# ArduiPi.net
KiCad netlist of a schematic drawn in EAGLE
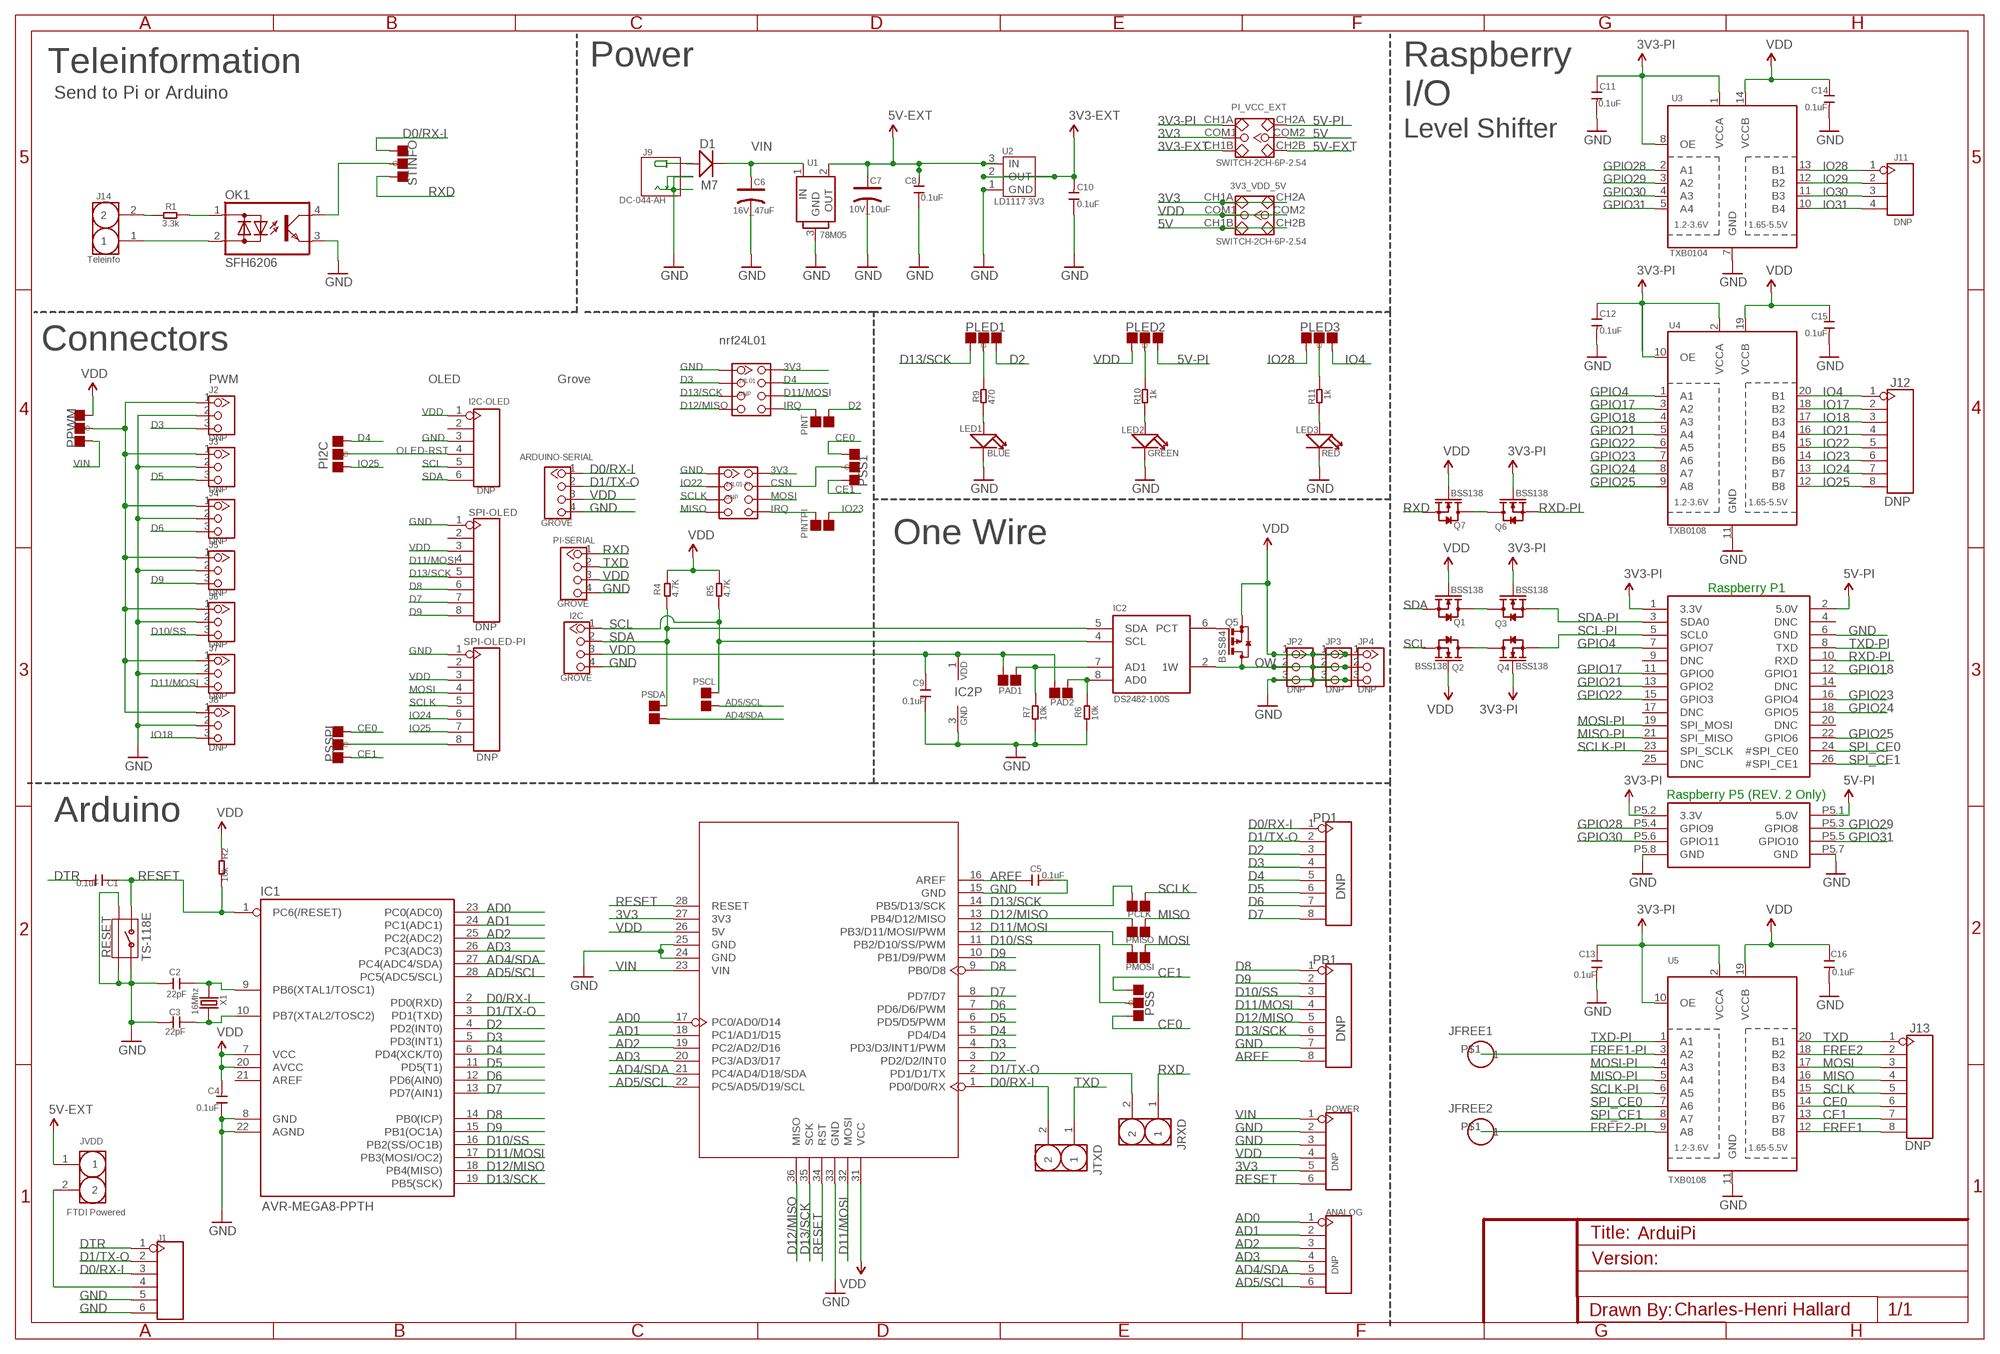
[diagram p0: schematic, sheet 1]

(export (version "E")
  (design (tool "Eeschema 10.0.6"))
  (components
    (comp (ref "3V3_VDD_5V")
      (value "SWITCH-2CH-6P-2.54")
      (footprint "eagle-import:6P-2CH-2.54-7.6X3.0")
      (libsource (lib "eagle-import") (part "SWITCH-2CH-6P"))
    )
    (comp (ref "24L01")
      (value "DNP")
      (footprint "eagle-import:2X4P-2.54")
      (libsource (lib "eagle-import") (part "HEADER-2X4P-2.54"))
    )
    (comp (ref "24L01-PI")
      (value "DNP")
      (footprint "eagle-import:2X4P-2.54")
      (libsource (lib "eagle-import") (part "HEADER-2X4P-2.54"))
    )
    (comp (ref "ANALOG")
      (value "DNP")
      (footprint "eagle-import:6P-2.54-65_35MIL")
      (libsource (lib "eagle-import") (part "HEADER-6P-65/35MIL"))
    )
    (comp (ref "ARDUINO-SERIAL")
      (value "GROVE")
      (footprint "eagle-import:4P-LEADED-2.0")
      (libsource (lib "eagle-import") (part "TWIG-2.0-LEADED"))
    )
    (comp (ref "C1")
      (value "0.1uF")
      (footprint "eagle-import:C0603")
      (libsource (lib "eagle-import") (part "C-0603"))
    )
    (comp (ref "C2")
      (value "22pF")
      (footprint "eagle-import:C0603")
      (libsource (lib "eagle-import") (part "C-0603"))
    )
    (comp (ref "C3")
      (value "22pF")
      (footprint "eagle-import:C0603")
      (libsource (lib "eagle-import") (part "C-0603"))
    )
    (comp (ref "C4")
      (value "0.1uF")
      (footprint "eagle-import:C0603")
      (libsource (lib "eagle-import") (part "C-0603"))
    )
    (comp (ref "C5")
      (value "0.1uF")
      (footprint "eagle-import:C0603")
      (libsource (lib "eagle-import") (part "C-0603"))
    )
    (comp (ref "C6")
      (value "16V_47uF")
      (footprint "eagle-import:AVX-C")
      (libsource (lib "eagle-import") (part "CAP-AVX-C"))
    )
    (comp (ref "C7")
      (value "10V_10uF")
      (footprint "eagle-import:AVX-A")
      (libsource (lib "eagle-import") (part "CAP-AVX-A"))
    )
    (comp (ref "C8")
      (value "0.1uF")
      (footprint "eagle-import:C0603")
      (libsource (lib "eagle-import") (part "C-0603"))
    )
    (comp (ref "C9")
      (value "0.1uF")
      (footprint "eagle-import:C0603")
      (libsource (lib "eagle-import") (part "C-0603"))
    )
    (comp (ref "C10")
      (value "0.1uF")
      (footprint "eagle-import:C0603")
      (libsource (lib "eagle-import") (part "C-0603"))
    )
    (comp (ref "C11")
      (value "0.1uF")
      (footprint "eagle-import:C0603")
      (libsource (lib "eagle-import") (part "C-0603"))
    )
    (comp (ref "C12")
      (value "0.1uF")
      (footprint "eagle-import:C0603")
      (libsource (lib "eagle-import") (part "C-0603"))
    )
    (comp (ref "C13")
      (value "0.1uF")
      (footprint "eagle-import:C0603")
      (libsource (lib "eagle-import") (part "C-0603"))
    )
    (comp (ref "C14")
      (value "0.1uF")
      (footprint "eagle-import:C0603")
      (libsource (lib "eagle-import") (part "C-0603"))
    )
    (comp (ref "C15")
      (value "0.1uF")
      (footprint "eagle-import:C0603")
      (libsource (lib "eagle-import") (part "C-0603"))
    )
    (comp (ref "C16")
      (value "0.1uF")
      (footprint "eagle-import:C0603")
      (libsource (lib "eagle-import") (part "C-0603"))
    )
    (comp (ref "D1")
      (value "M7")
      (footprint "eagle-import:D2010")
      (libsource (lib "eagle-import") (part "D'SMA'"))
    )
    (comp (ref "I2C")
      (value "GROVE")
      (footprint "eagle-import:4P-LEADED-2.0")
      (libsource (lib "eagle-import") (part "TWIG-2.0-LEADED"))
    )
    (comp (ref "I2C-OLED")
      (value "DNP")
      (footprint "eagle-import:6P-2.54-65_35MIL")
      (libsource (lib "eagle-import") (part "HEADER-6P-65/35MIL"))
    )
    (comp (ref "IC1")
      (value "AVR-MEGA8-PPTH")
      (footprint "eagle-import:DIL28-3")
      (libsource (lib "eagle-import") (part "AVR-MEGA8-PPTH"))
    )
    (comp (ref "IC2")
      (value "DS2482-100S")
      (footprint "eagle-import:SO08")
      (libsource (lib "eagle-import") (part "DS2482-100S"))
    )
    (comp (ref "J1")
      (value "HEADER-6P-65/35MIL")
      (footprint "eagle-import:6P-2.54-65_35MIL")
      (libsource (lib "eagle-import") (part "HEADER-6P-65/35MIL"))
    )
    (comp (ref "J2")
      (value "DNP")
      (footprint "eagle-import:3P-2.54")
      (libsource (lib "eagle-import") (part "HEADER-3P-2.54"))
    )
    (comp (ref "J3")
      (value "DNP")
      (footprint "eagle-import:3P-2.54")
      (libsource (lib "eagle-import") (part "HEADER-3P-2.54"))
    )
    (comp (ref "J4")
      (value "DNP")
      (footprint "eagle-import:3P-2.54")
      (libsource (lib "eagle-import") (part "HEADER-3P-2.54"))
    )
    (comp (ref "J5")
      (value "DNP")
      (footprint "eagle-import:3P-2.54")
      (libsource (lib "eagle-import") (part "HEADER-3P-2.54"))
    )
    (comp (ref "J6")
      (value "DNP")
      (footprint "eagle-import:3P-2.54")
      (libsource (lib "eagle-import") (part "HEADER-3P-2.54"))
    )
    (comp (ref "J7")
      (value "DNP")
      (footprint "eagle-import:3P-2.54")
      (libsource (lib "eagle-import") (part "HEADER-3P-2.54"))
    )
    (comp (ref "J8")
      (value "DNP")
      (footprint "eagle-import:3P-2.54")
      (libsource (lib "eagle-import") (part "HEADER-3P-2.54"))
    )
    (comp (ref "J9")
      (value "DC-044-AH")
      (footprint "eagle-import:DC-044")
      (libsource (lib "eagle-import") (part "JACK-DC-044"))
    )
    (comp (ref "J11")
      (value "DNP")
      (footprint "eagle-import:4P-65_35MIL")
      (libsource (lib "eagle-import") (part "HEADER-4P-65/35MIL"))
    )
    (comp (ref "J12")
      (value "DNP")
      (footprint "eagle-import:8P-2.54-65_35MIL")
      (libsource (lib "eagle-import") (part "HEADER-8P-65/35MIL"))
    )
    (comp (ref "J13")
      (value "DNP")
      (footprint "eagle-import:8P-2.54-65_35MIL")
      (libsource (lib "eagle-import") (part "HEADER-8P-65/35MIL"))
    )
    (comp (ref "J14")
      (value "Teleinfo")
      (footprint "eagle-import:2P-2.54")
      (libsource (lib "eagle-import") (part "HEADER-2P-2.54"))
    )
    (comp (ref "JFREE1")
      (value "HEADER-1P-32")
      (footprint "eagle-import:1P-60_32MIL")
      (libsource (lib "eagle-import") (part "HEADER-1P-32"))
    )
    (comp (ref "JFREE2")
      (value "HEADER-1P-32")
      (footprint "eagle-import:1P-60_32MIL")
      (libsource (lib "eagle-import") (part "HEADER-1P-32"))
    )
    (comp (ref "JP2")
      (value "DNP")
      (footprint "eagle-import:3P-2.54")
      (libsource (lib "eagle-import") (part "HEADER-3P-2.54"))
    )
    (comp (ref "JP3")
      (value "DNP")
      (footprint "eagle-import:3P-2.54")
      (libsource (lib "eagle-import") (part "HEADER-3P-2.54"))
    )
    (comp (ref "JP4")
      (value "DNP")
      (footprint "eagle-import:3P-2.54")
      (libsource (lib "eagle-import") (part "HEADER-3P-2.54"))
    )
    (comp (ref "JRXD")
      (value "J2")
      (footprint "eagle-import:2P-2.54")
      (libsource (lib "eagle-import") (part "HEADER-2P-2.54"))
    )
    (comp (ref "JTXD")
      (value "J1")
      (footprint "eagle-import:2P-2.54")
      (libsource (lib "eagle-import") (part "HEADER-2P-2.54"))
    )
    (comp (ref "JVDD")
      (value "FTDI Powered")
      (footprint "eagle-import:2P-2.54")
      (libsource (lib "eagle-import") (part "HEADER-2P-2.54"))
    )
    (comp (ref "LED1")
      (value "BLUE")
      (footprint "eagle-import:LED-0603")
      (libsource (lib "eagle-import") (part "LED'0603'"))
    )
    (comp (ref "LED2")
      (value "GREEN")
      (footprint "eagle-import:LED-0603")
      (libsource (lib "eagle-import") (part "LED'0603'"))
    )
    (comp (ref "LED3")
      (value "RED")
      (footprint "eagle-import:LED-0603")
      (libsource (lib "eagle-import") (part "LED'0603'"))
    )
    (comp (ref "OK1")
      (value "SFH6206")
      (footprint "eagle-import:DIL4-SMD")
      (fields (field (name "MF") "VISHAY/TELEFUNKEN") (field (name "MPN") "SFH6206-3"))
      (libsource (lib "eagle-import") (part "SFH6206"))
    )
    (comp (ref "PAD1")
      (value "PAD1")
      (footprint "eagle-import:2P-SMD-1.78X1.27")
      (fields (field (name "PARTNO") "DNP") (field (name "PARTNO_1") "DNP"))
      (libsource (lib "eagle-import") (part "PAD-JUMPER-2P"))
    )
    (comp (ref "PAD2")
      (value "PAD2")
      (footprint "eagle-import:2P-SMD-1.78X1.27")
      (fields (field (name "PARTNO") "DNP") (field (name "PARTNO_1") "DNP"))
      (libsource (lib "eagle-import") (part "PAD-JUMPER-2P"))
    )
    (comp (ref "PB1")
      (value "DNP")
      (footprint "eagle-import:8P-2.54-65_35MIL")
      (libsource (lib "eagle-import") (part "HEADER-8P-65/35MIL"))
    )
    (comp (ref "PCLK")
      (value "PCLK")
      (footprint "eagle-import:2P-SMD-1.78X1.27")
      (fields (field (name "PARTNO") "DNP"))
      (libsource (lib "eagle-import") (part "PAD-JUMPER-2P"))
    )
    (comp (ref "PD1")
      (value "DNP")
      (footprint "eagle-import:8P-2.54-65_35MIL")
      (libsource (lib "eagle-import") (part "HEADER-8P-65/35MIL"))
    )
    (comp (ref "PI-P1")
      (value "PI-P1")
      (footprint "eagle-import:RASPBERRYPI_SHIELD")
      (libsource (lib "eagle-import") (part "RASPBERRYPI_BV2"))
    )
    (comp (ref "PI-SERIAL")
      (value "GROVE")
      (footprint "eagle-import:4P-LEADED-2.0")
      (libsource (lib "eagle-import") (part "TWIG-2.0-LEADED"))
    )
    (comp (ref "PI2C")
      (value "PAD-JUMPER-3P-40*40")
      (footprint "eagle-import:3P-SMD-4.1X1.5")
      (fields (field (name "PARTNO") "DNP") (field (name "PARTNO_1") "DNP"))
      (libsource (lib "eagle-import") (part "PAD-JUMPER-3P-4040"))
    )
    (comp (ref "PINT")
      (value "PINT")
      (footprint "eagle-import:2P-SMD-1.78X1.27")
      (fields (field (name "PARTNO") "DNP"))
      (libsource (lib "eagle-import") (part "PAD-JUMPER-2P"))
    )
    (comp (ref "PINTPI")
      (value "PINTPI")
      (footprint "eagle-import:2P-SMD-1.78X1.27")
      (fields (field (name "PARTNO") "DNP"))
      (libsource (lib "eagle-import") (part "PAD-JUMPER-2P"))
    )
    (comp (ref "PI_VCC_EXT")
      (value "SWITCH-2CH-6P-2.54")
      (footprint "eagle-import:6P-2CH-2.54-7.6X3.0")
      (libsource (lib "eagle-import") (part "SWITCH-2CH-6P"))
    )
    (comp (ref "PLED1")
      (value "PAD-JUMPER-3P-40*40")
      (footprint "eagle-import:3P-SMD-4.1X1.5")
      (fields (field (name "PARTNO") "DNP") (field (name "PARTNO_1") "DNP"))
      (libsource (lib "eagle-import") (part "PAD-JUMPER-3P-4040"))
    )
    (comp (ref "PLED2")
      (value "PAD-JUMPER-3P-40*40")
      (footprint "eagle-import:3P-SMD-4.1X1.5")
      (fields (field (name "PARTNO") "DNP"))
      (libsource (lib "eagle-import") (part "PAD-JUMPER-3P-4040"))
    )
    (comp (ref "PLED3")
      (value "PAD-JUMPER-3P-40*40")
      (footprint "eagle-import:3P-SMD-4.1X1.5")
      (fields (field (name "PARTNO") "DNP") (field (name "PARTNO_1") "DNP"))
      (libsource (lib "eagle-import") (part "PAD-JUMPER-3P-4040"))
    )
    (comp (ref "PMISO")
      (value "PMISO")
      (footprint "eagle-import:2P-SMD-1.78X1.27")
      (fields (field (name "PARTNO") "DNP"))
      (libsource (lib "eagle-import") (part "PAD-JUMPER-2P"))
    )
    (comp (ref "PMOSI")
      (value "PMOSI")
      (footprint "eagle-import:2P-SMD-1.78X1.27")
      (fields (field (name "PARTNO") "DNP"))
      (libsource (lib "eagle-import") (part "PAD-JUMPER-2P"))
    )
    (comp (ref "POWER")
      (value "DNP")
      (footprint "eagle-import:6P-2.54-65_35MIL")
      (libsource (lib "eagle-import") (part "HEADER-6P-65/35MIL"))
    )
    (comp (ref "PPWM")
      (value "PAD-JUMPER-3P-40*40")
      (footprint "eagle-import:3P-SMD-4.1X1.5")
      (fields (field (name "PARTNO") "DNP") (field (name "PARTNO_1") "DNP"))
      (libsource (lib "eagle-import") (part "PAD-JUMPER-3P-4040"))
    )
    (comp (ref "PSCL")
      (value "PSCL")
      (footprint "eagle-import:2P-SMD-1.78X1.27")
      (fields (field (name "PARTNO") "DNP"))
      (libsource (lib "eagle-import") (part "PAD-JUMPER-2P"))
    )
    (comp (ref "PSDA")
      (value "PSDA")
      (footprint "eagle-import:2P-SMD-1.78X1.27")
      (fields (field (name "PARTNO") "DNP"))
      (libsource (lib "eagle-import") (part "PAD-JUMPER-2P"))
    )
    (comp (ref "PSS")
      (value "PAD-JUMPER-3P-40*40")
      (footprint "eagle-import:3P-SMD-4.1X1.5")
      (fields (field (name "PARTNO") "DNP"))
      (libsource (lib "eagle-import") (part "PAD-JUMPER-3P-4040"))
    )
    (comp (ref "PSS1")
      (value "PAD-JUMPER-3P-40*40")
      (footprint "eagle-import:3P-SMD-4.1X1.5")
      (fields (field (name "PARTNO") "DNP") (field (name "PARTNO_1") "DNP"))
      (libsource (lib "eagle-import") (part "PAD-JUMPER-3P-4040"))
    )
    (comp (ref "PSSPI")
      (value "PAD-JUMPER-3P-40*40")
      (footprint "eagle-import:3P-SMD-4.1X1.5")
      (fields (field (name "PARTNO") "DNP") (field (name "PARTNO_1") "DNP"))
      (libsource (lib "eagle-import") (part "PAD-JUMPER-3P-4040"))
    )
    (comp (ref "Q1")
      (value "BSS138")
      (footprint "eagle-import:SOT23")
      (libsource (lib "eagle-import") (part "MOSFET-N-SOT23"))
    )
    (comp (ref "Q2")
      (value "BSS138")
      (footprint "eagle-import:SOT23")
      (libsource (lib "eagle-import") (part "MOSFET-N-SOT23"))
    )
    (comp (ref "Q3")
      (value "BSS138")
      (footprint "eagle-import:SOT23")
      (libsource (lib "eagle-import") (part "MOSFET-N-SOT23"))
    )
    (comp (ref "Q4")
      (value "BSS138")
      (footprint "eagle-import:SOT23")
      (libsource (lib "eagle-import") (part "MOSFET-N-SOT23"))
    )
    (comp (ref "Q5")
      (value "BSS84")
      (footprint "eagle-import:SOT23")
      (libsource (lib "eagle-import") (part "BSS84"))
    )
    (comp (ref "Q6")
      (value "BSS138")
      (footprint "eagle-import:SOT23")
      (libsource (lib "eagle-import") (part "MOSFET-N-SOT23"))
    )
    (comp (ref "Q7")
      (value "BSS138")
      (footprint "eagle-import:SOT23")
      (libsource (lib "eagle-import") (part "MOSFET-N-SOT23"))
    )
    (comp (ref "R1")
      (value "3.3k")
      (footprint "eagle-import:R0603")
      (libsource (lib "eagle-import") (part "R-0603"))
    )
    (comp (ref "R2")
      (value "10k")
      (footprint "eagle-import:R0603")
      (libsource (lib "eagle-import") (part "R-0603"))
    )
    (comp (ref "R4")
      (value "4.7K")
      (footprint "eagle-import:R0603")
      (libsource (lib "eagle-import") (part "R-0603"))
    )
    (comp (ref "R5")
      (value "4.7K")
      (footprint "eagle-import:R0603")
      (libsource (lib "eagle-import") (part "R-0603"))
    )
    (comp (ref "R6")
      (value "10k")
      (footprint "eagle-import:R0603")
      (libsource (lib "eagle-import") (part "R-0603"))
    )
    (comp (ref "R7")
      (value "10k")
      (footprint "eagle-import:R0603")
      (libsource (lib "eagle-import") (part "R-0603"))
    )
    (comp (ref "R9")
      (value "470")
      (footprint "eagle-import:R0603")
      (libsource (lib "eagle-import") (part "R-0603"))
    )
    (comp (ref "R10")
      (value "1k")
      (footprint "eagle-import:R0603")
      (libsource (lib "eagle-import") (part "R-0603"))
    )
    (comp (ref "R11")
      (value "1k")
      (footprint "eagle-import:R0603")
      (libsource (lib "eagle-import") (part "R-0603"))
    )
    (comp (ref "RESET")
      (value "TS-118E")
      (footprint "eagle-import:4P-SMD-7X3.5X3.5H")
      (libsource (lib "eagle-import") (part "BUTTON-4P-REINFORCE'TS-118E'"))
    )
    (comp (ref "SPI-OLED")
      (value "DNP")
      (footprint "eagle-import:8P-2.54-65_35MIL")
      (libsource (lib "eagle-import") (part "HEADER-8P-65/35MIL"))
    )
    (comp (ref "SPI-OLED-PI")
      (value "DNP")
      (footprint "eagle-import:8P-2.54-65_35MIL")
      (libsource (lib "eagle-import") (part "HEADER-8P-65/35MIL"))
    )
    (comp (ref "STINFO")
      (value "PAD-JUMPER-3P-40*40")
      (footprint "eagle-import:3P-SMD-4.1X1.5")
      (fields (field (name "PARTNO") "DNP"))
      (libsource (lib "eagle-import") (part "PAD-JUMPER-3P-4040"))
    )
    (comp (ref "U1")
      (value "78M05")
      (footprint "eagle-import:TO252")
      (libsource (lib "eagle-import") (part "78M05-TO252"))
    )
    (comp (ref "U2")
      (value "LD1117 3V3")
      (footprint "eagle-import:SOT-223")
      (libsource (lib "eagle-import") (part "LD1117SOT223"))
    )
    (comp (ref "U3")
      (value "TXB0104")
      (footprint "eagle-import:TSSOP14")
      (libsource (lib "eagle-import") (part "TXB0104PWR"))
    )
    (comp (ref "U4")
      (value "TXB0108")
      (footprint "eagle-import:TSSOP20")
      (libsource (lib "eagle-import") (part "TXB0108PWR"))
    )
    (comp (ref "U5")
      (value "TXB0108")
      (footprint "eagle-import:TSSOP20")
      (libsource (lib "eagle-import") (part "TXB0108PWR"))
    )
    (comp (ref "U6")
      (value "ARDUINO'W/-SILK")
      (footprint "eagle-import:ARDUINO")
      (libsource (lib "eagle-import") (part "ARDUINO'W/-SILK"))
    )
    (comp (ref "X1")
      (value "16Mhz")
      (footprint "eagle-import:2P-SMD-5X3.2")
      (libsource (lib "eagle-import") (part "CRYSTAL'5032'"))
    )
  )
  (nets
    (net (code "1") (name "/3V3") (class "Default")
      (node (ref "24L01") (pin "8") (pinfunction "8_8") (pintype "bidirectional"))
      (node (ref "24L01-PI") (pin "8") (pinfunction "8_8") (pintype "bidirectional"))
      (node (ref "3V3_VDD_5V") (pin "CH1A") (pinfunction "CH1A_CH1A") (pintype "bidirectional"))
      (node (ref "3V3_VDD_5V") (pin "CH2A") (pinfunction "CH2A_CH2A") (pintype "bidirectional"))
      (node (ref "PI_VCC_EXT") (pin "COM1") (pinfunction "COM1_COM1") (pintype "bidirectional"))
      (node (ref "POWER") (pin "5") (pinfunction "5_5") (pintype "bidirectional"))
      (node (ref "U6") (pin "27") (pinfunction "3V3_27") (pintype "bidirectional"))
    )
    (net (code "2") (name "/5V") (class "Default")
      (node (ref "3V3_VDD_5V") (pin "CH1B") (pinfunction "CH1B_CH1B") (pintype "bidirectional"))
      (node (ref "3V3_VDD_5V") (pin "CH2B") (pinfunction "CH2B_CH2B") (pintype "bidirectional"))
      (node (ref "PI_VCC_EXT") (pin "COM2") (pinfunction "COM2_COM2") (pintype "bidirectional"))
    )
    (net (code "3") (name "/AD0") (class "Default")
      (node (ref "ANALOG") (pin "1") (pinfunction "1_1") (pintype "bidirectional"))
      (node (ref "IC1") (pin "23") (pinfunction "PC0(ADC0)_23") (pintype "bidirectional"))
      (node (ref "U6") (pin "17") (pinfunction "PC0/AD0/D14_17") (pintype "bidirectional"))
    )
    (net (code "4") (name "/AD1") (class "Default")
      (node (ref "ANALOG") (pin "2") (pinfunction "2_2") (pintype "bidirectional"))
      (node (ref "IC1") (pin "24") (pinfunction "PC1(ADC1)_24") (pintype "bidirectional"))
      (node (ref "U6") (pin "18") (pinfunction "PC1/AD1/D15_18") (pintype "bidirectional"))
    )
    (net (code "5") (name "/AD2") (class "Default")
      (node (ref "ANALOG") (pin "3") (pinfunction "3_3") (pintype "bidirectional"))
      (node (ref "IC1") (pin "25") (pinfunction "PC2(ADC2)_25") (pintype "bidirectional"))
      (node (ref "U6") (pin "19") (pinfunction "PC2/AD2/D16_19") (pintype "bidirectional"))
    )
    (net (code "6") (name "/AD3") (class "Default")
      (node (ref "ANALOG") (pin "4") (pinfunction "4_4") (pintype "bidirectional"))
      (node (ref "IC1") (pin "26") (pinfunction "PC3(ADC3)_26") (pintype "bidirectional"))
      (node (ref "U6") (pin "20") (pinfunction "PC3/AD3/D17_20") (pintype "bidirectional"))
    )
    (net (code "7") (name "/AD4{slash}SDA") (class "Default")
      (node (ref "ANALOG") (pin "5") (pinfunction "5_5") (pintype "bidirectional"))
      (node (ref "IC1") (pin "27") (pinfunction "PC4(ADC4/SDA)_27") (pintype "bidirectional"))
      (node (ref "PSDA") (pin "1") (pinfunction "1_1") (pintype "bidirectional"))
      (node (ref "U6") (pin "21") (pinfunction "PC4/AD4/D18/SDA_21") (pintype "bidirectional"))
    )
    (net (code "8") (name "/AD5{slash}SCL") (class "Default")
      (node (ref "ANALOG") (pin "6") (pinfunction "6_6") (pintype "bidirectional"))
      (node (ref "IC1") (pin "28") (pinfunction "PC5(ADC5/SCL)_28") (pintype "bidirectional"))
      (node (ref "PSCL") (pin "1") (pinfunction "1_1") (pintype "bidirectional"))
      (node (ref "U6") (pin "22") (pinfunction "PC5/AD5/D19/SCL_22") (pintype "bidirectional"))
    )
    (net (code "9") (name "/AREF") (class "Default")
      (node (ref "C5") (pin "1") (pinfunction "1_1") (pintype "passive"))
      (node (ref "PB1") (pin "8") (pinfunction "8_8") (pintype "bidirectional"))
      (node (ref "U6") (pin "16") (pinfunction "AREF_16") (pintype "bidirectional"))
    )
    (net (code "10") (name "/CE0") (class "Default")
      (node (ref "J13") (pin "6") (pinfunction "6_6") (pintype "bidirectional"))
      (node (ref "PSS") (pin "11") (pinfunction "R_11") (pintype "bidirectional"))
      (node (ref "PSS1") (pin "00") (pinfunction "L_00") (pintype "bidirectional"))
      (node (ref "PSSPI") (pin "11") (pinfunction "R_11") (pintype "bidirectional"))
      (node (ref "U5") (pin "14") (pinfunction "B6_14") (pintype "bidirectional"))
    )
    (net (code "11") (name "/CE1") (class "Default")
      (node (ref "J13") (pin "7") (pinfunction "7_7") (pintype "bidirectional"))
      (node (ref "PSS") (pin "00") (pinfunction "L_00") (pintype "bidirectional"))
      (node (ref "PSS1") (pin "11") (pinfunction "R_11") (pintype "bidirectional"))
      (node (ref "PSSPI") (pin "00") (pinfunction "L_00") (pintype "bidirectional"))
      (node (ref "U5") (pin "13") (pinfunction "B7_13") (pintype "bidirectional"))
    )
    (net (code "12") (name "/CSN") (class "Default")
      (node (ref "24L01-PI") (pin "7") (pinfunction "7_7") (pintype "bidirectional"))
      (node (ref "PSS1") (pin "MM") (pinfunction "C_MM") (pintype "bidirectional"))
    )
    (net (code "13") (name "/D0{slash}RX-I") (class "Default")
      (node (ref "ARDUINO-SERIAL") (pin "1") (pinfunction "1_1") (pintype "bidirectional"))
      (node (ref "IC1") (pin "2") (pinfunction "PD0(RXD)_2") (pintype "bidirectional"))
      (node (ref "J1") (pin "3") (pinfunction "3_3") (pintype "bidirectional"))
      (node (ref "JTXD") (pin "2") (pinfunction "2_2") (pintype "bidirectional"))
      (node (ref "PD1") (pin "1") (pinfunction "1_1") (pintype "bidirectional"))
      (node (ref "STINFO") (pin "00") (pinfunction "L_00") (pintype "bidirectional"))
      (node (ref "U6") (pin "1") (pinfunction "PD0/D0/RX_1") (pintype "bidirectional"))
    )
    (net (code "14") (name "/D1{slash}TX-O") (class "Default")
      (node (ref "ARDUINO-SERIAL") (pin "2") (pinfunction "2_2") (pintype "bidirectional"))
      (node (ref "IC1") (pin "3") (pinfunction "PD1(TXD)_3") (pintype "bidirectional"))
      (node (ref "J1") (pin "2") (pinfunction "2_2") (pintype "bidirectional"))
      (node (ref "JRXD") (pin "2") (pinfunction "2_2") (pintype "bidirectional"))
      (node (ref "PD1") (pin "2") (pinfunction "2_2") (pintype "bidirectional"))
      (node (ref "U6") (pin "2") (pinfunction "PD1/D1/TX_2") (pintype "bidirectional"))
    )
    (net (code "15") (name "/D2") (class "Default")
      (node (ref "IC1") (pin "4") (pinfunction "PD2(INT0)_4") (pintype "bidirectional"))
      (node (ref "PD1") (pin "3") (pinfunction "3_3") (pintype "bidirectional"))
      (node (ref "PINT") (pin "1") (pinfunction "1_1") (pintype "bidirectional"))
      (node (ref "PLED1") (pin "11") (pinfunction "R_11") (pintype "bidirectional"))
      (node (ref "U6") (pin "3") (pinfunction "PD2/D2/INT0_3") (pintype "bidirectional"))
    )
    (net (code "16") (name "/D3") (class "Default")
      (node (ref "24L01") (pin "2") (pinfunction "2_2") (pintype "bidirectional"))
      (node (ref "IC1") (pin "5") (pinfunction "PD3(INT1)_5") (pintype "bidirectional"))
      (node (ref "J2") (pin "3") (pinfunction "P$3_3") (pintype "bidirectional"))
      (node (ref "PD1") (pin "4") (pinfunction "4_4") (pintype "bidirectional"))
      (node (ref "U6") (pin "4") (pinfunction "PD3/D3/INT1/PWM_4") (pintype "bidirectional"))
    )
    (net (code "17") (name "/D4") (class "Default")
      (node (ref "24L01") (pin "7") (pinfunction "7_7") (pintype "bidirectional"))
      (node (ref "IC1") (pin "6") (pinfunction "PD4(XCK/T0)_6") (pintype "bidirectional"))
      (node (ref "PD1") (pin "5") (pinfunction "5_5") (pintype "bidirectional"))
      (node (ref "PI2C") (pin "11") (pinfunction "R_11") (pintype "bidirectional"))
      (node (ref "U6") (pin "5") (pinfunction "PD4/D4_5") (pintype "bidirectional"))
    )
    (net (code "18") (name "/D5") (class "Default")
      (node (ref "IC1") (pin "11") (pinfunction "PD5(T1)_11") (pintype "bidirectional"))
      (node (ref "J3") (pin "3") (pinfunction "P$3_3") (pintype "bidirectional"))
      (node (ref "PD1") (pin "6") (pinfunction "6_6") (pintype "bidirectional"))
      (node (ref "U6") (pin "6") (pinfunction "PD5/D5/PWM_6") (pintype "bidirectional"))
    )
    (net (code "19") (name "/D6") (class "Default")
      (node (ref "IC1") (pin "12") (pinfunction "PD6(AIN0)_12") (pintype "bidirectional"))
      (node (ref "J4") (pin "3") (pinfunction "P$3_3") (pintype "bidirectional"))
      (node (ref "PD1") (pin "7") (pinfunction "7_7") (pintype "bidirectional"))
      (node (ref "U6") (pin "7") (pinfunction "PD6/D6/PWM_7") (pintype "bidirectional"))
    )
    (net (code "20") (name "/D7") (class "Default")
      (node (ref "IC1") (pin "13") (pinfunction "PD7(AIN1)_13") (pintype "bidirectional"))
      (node (ref "PD1") (pin "8") (pinfunction "8_8") (pintype "bidirectional"))
      (node (ref "SPI-OLED") (pin "7") (pinfunction "7_7") (pintype "bidirectional"))
      (node (ref "U6") (pin "8") (pinfunction "PD7/D7_8") (pintype "bidirectional"))
    )
    (net (code "21") (name "/D8") (class "Default")
      (node (ref "IC1") (pin "14") (pinfunction "PB0(ICP)_14") (pintype "bidirectional"))
      (node (ref "PB1") (pin "1") (pinfunction "1_1") (pintype "bidirectional"))
      (node (ref "SPI-OLED") (pin "6") (pinfunction "6_6") (pintype "bidirectional"))
      (node (ref "U6") (pin "9") (pinfunction "PB0/D8_9") (pintype "bidirectional"))
    )
    (net (code "22") (name "/D9") (class "Default")
      (node (ref "IC1") (pin "15") (pinfunction "PB1(OC1A)_15") (pintype "bidirectional"))
      (node (ref "J5") (pin "3") (pinfunction "P$3_3") (pintype "bidirectional"))
      (node (ref "PB1") (pin "2") (pinfunction "2_2") (pintype "bidirectional"))
      (node (ref "SPI-OLED") (pin "8") (pinfunction "8_8") (pintype "bidirectional"))
      (node (ref "U6") (pin "10") (pinfunction "PB1/D9/PWM_10") (pintype "bidirectional"))
    )
    (net (code "23") (name "/D10{slash}SS") (class "Default")
      (node (ref "IC1") (pin "16") (pinfunction "PB2(SS/OC1B)_16") (pintype "bidirectional"))
      (node (ref "J6") (pin "3") (pinfunction "P$3_3") (pintype "bidirectional"))
      (node (ref "PB1") (pin "3") (pinfunction "3_3") (pintype "bidirectional"))
      (node (ref "PSS") (pin "MM") (pinfunction "C_MM") (pintype "bidirectional"))
      (node (ref "U6") (pin "11") (pinfunction "PB2/D10/SS/PWM_11") (pintype "bidirectional"))
    )
    (net (code "24") (name "/D11{slash}MOSI") (class "Default")
      (node (ref "24L01") (pin "6") (pinfunction "6_6") (pintype "bidirectional"))
      (node (ref "IC1") (pin "17") (pinfunction "PB3(MOSI/OC2)_17") (pintype "bidirectional"))
      (node (ref "J7") (pin "3") (pinfunction "P$3_3") (pintype "bidirectional"))
      (node (ref "PB1") (pin "4") (pinfunction "4_4") (pintype "bidirectional"))
      (node (ref "PMOSI") (pin "2") (pinfunction "2_2") (pintype "bidirectional"))
      (node (ref "SPI-OLED") (pin "4") (pinfunction "4_4") (pintype "bidirectional"))
      (node (ref "U6") (pin "12") (pinfunction "PB3/D11/MOSI/PWM_12") (pintype "bidirectional"))
      (node (ref "U6") (pin "32") (pinfunction "MOSI_32") (pintype "bidirectional"))
    )
    (net (code "25") (name "/D12{slash}MISO") (class "Default")
      (node (ref "24L01") (pin "4") (pinfunction "4_4") (pintype "bidirectional"))
      (node (ref "IC1") (pin "18") (pinfunction "PB4(MISO)_18") (pintype "bidirectional"))
      (node (ref "PB1") (pin "5") (pinfunction "5_5") (pintype "bidirectional"))
      (node (ref "PMISO") (pin "2") (pinfunction "2_2") (pintype "bidirectional"))
      (node (ref "U6") (pin "13") (pinfunction "PB4/D12/MISO_13") (pintype "bidirectional"))
      (node (ref "U6") (pin "36") (pinfunction "MISO_36") (pintype "bidirectional"))
    )
    (net (code "26") (name "/D13{slash}SCK") (class "Default")
      (node (ref "24L01") (pin "3") (pinfunction "3_3") (pintype "bidirectional"))
      (node (ref "IC1") (pin "19") (pinfunction "PB5(SCK)_19") (pintype "bidirectional"))
      (node (ref "PB1") (pin "6") (pinfunction "6_6") (pintype "bidirectional"))
      (node (ref "PCLK") (pin "2") (pinfunction "2_2") (pintype "bidirectional"))
      (node (ref "PLED1") (pin "00") (pinfunction "L_00") (pintype "bidirectional"))
      (node (ref "SPI-OLED") (pin "5") (pinfunction "5_5") (pintype "bidirectional"))
      (node (ref "U6") (pin "14") (pinfunction "PB5/D13/SCK_14") (pintype "bidirectional"))
      (node (ref "U6") (pin "35") (pinfunction "SCK_35") (pintype "bidirectional"))
    )
    (net (code "27") (name "/DTR") (class "Default")
      (node (ref "C1") (pin "2") (pinfunction "2_2") (pintype "passive"))
      (node (ref "J1") (pin "1") (pinfunction "1_1") (pintype "bidirectional"))
    )
    (net (code "28") (name "/FREE1") (class "Default")
      (node (ref "J13") (pin "8") (pinfunction "8_8") (pintype "bidirectional"))
      (node (ref "U5") (pin "12") (pinfunction "B8_12") (pintype "bidirectional"))
    )
    (net (code "29") (name "/FREE1-PI") (class "Default")
      (node (ref "JFREE1") (pin "P$1") (pinfunction "1_P$1") (pintype "bidirectional"))
      (node (ref "U5") (pin "3") (pinfunction "A2_3") (pintype "bidirectional"))
    )
    (net (code "30") (name "/FREE2") (class "Default")
      (node (ref "J13") (pin "2") (pinfunction "2_2") (pintype "bidirectional"))
      (node (ref "U5") (pin "18") (pinfunction "B2_18") (pintype "bidirectional"))
    )
    (net (code "31") (name "/FREE2-PI") (class "Default")
      (node (ref "JFREE2") (pin "P$1") (pinfunction "1_P$1") (pintype "bidirectional"))
      (node (ref "U5") (pin "9") (pinfunction "A8_9") (pintype "bidirectional"))
    )
    (net (code "32") (name "/GPIO4") (class "Default")
      (node (ref "PI-P1") (pin "7") (pinfunction "GPIO7_7") (pintype "bidirectional"))
      (node (ref "U4") (pin "1") (pinfunction "A1_1") (pintype "bidirectional"))
    )
    (net (code "33") (name "/GPIO17") (class "Default")
      (node (ref "PI-P1") (pin "11") (pinfunction "GPIO0_11") (pintype "bidirectional"))
      (node (ref "U4") (pin "3") (pinfunction "A2_3") (pintype "bidirectional"))
    )
    (net (code "34") (name "/GPIO18") (class "Default")
      (node (ref "PI-P1") (pin "12") (pinfunction "GPIO1_12") (pintype "bidirectional"))
      (node (ref "U4") (pin "4") (pinfunction "A3_4") (pintype "bidirectional"))
    )
    (net (code "35") (name "/GPIO21") (class "Default")
      (node (ref "PI-P1") (pin "13") (pinfunction "GPIO2_13") (pintype "bidirectional"))
      (node (ref "U4") (pin "5") (pinfunction "A4_5") (pintype "bidirectional"))
    )
    (net (code "36") (name "/GPIO22") (class "Default")
      (node (ref "PI-P1") (pin "15") (pinfunction "GPIO3_15") (pintype "bidirectional"))
      (node (ref "U4") (pin "6") (pinfunction "A5_6") (pintype "bidirectional"))
    )
    (net (code "37") (name "/GPIO23") (class "Default")
      (node (ref "PI-P1") (pin "16") (pinfunction "GPIO4_16") (pintype "bidirectional"))
      (node (ref "U4") (pin "7") (pinfunction "A6_7") (pintype "bidirectional"))
    )
    (net (code "38") (name "/GPIO24") (class "Default")
      (node (ref "PI-P1") (pin "18") (pinfunction "GPIO5_18") (pintype "bidirectional"))
      (node (ref "U4") (pin "8") (pinfunction "A7_8") (pintype "bidirectional"))
    )
    (net (code "39") (name "/GPIO25") (class "Default")
      (node (ref "PI-P1") (pin "22") (pinfunction "GPIO6_22") (pintype "bidirectional"))
      (node (ref "U4") (pin "9") (pinfunction "A8_9") (pintype "bidirectional"))
    )
    (net (code "40") (name "/GPIO28") (class "Default")
      (node (ref "PI-P1") (pin "P5.4") (pinfunction "GPIO9_P5.4") (pintype "bidirectional"))
      (node (ref "U3") (pin "2") (pinfunction "A1_2") (pintype "bidirectional"))
    )
    (net (code "41") (name "/GPIO29") (class "Default")
      (node (ref "PI-P1") (pin "P5.3") (pinfunction "GPIO8_P5.3") (pintype "bidirectional"))
      (node (ref "U3") (pin "3") (pinfunction "A2_3") (pintype "bidirectional"))
    )
    (net (code "42") (name "/GPIO30") (class "Default")
      (node (ref "PI-P1") (pin "P5.6") (pinfunction "GPIO11_P5.6") (pintype "bidirectional"))
      (node (ref "U3") (pin "4") (pinfunction "A3_4") (pintype "bidirectional"))
    )
    (net (code "43") (name "/GPIO31") (class "Default")
      (node (ref "PI-P1") (pin "P5.5") (pinfunction "GPIO10_P5.5") (pintype "bidirectional"))
      (node (ref "U3") (pin "5") (pinfunction "A4_5") (pintype "bidirectional"))
    )
    (net (code "44") (name "/IO4") (class "Default")
      (node (ref "J12") (pin "1") (pinfunction "1_1") (pintype "bidirectional"))
      (node (ref "PLED3") (pin "11") (pinfunction "R_11") (pintype "bidirectional"))
      (node (ref "U4") (pin "20") (pinfunction "B1_20") (pintype "bidirectional"))
    )
    (net (code "45") (name "/IO17") (class "Default")
      (node (ref "J12") (pin "2") (pinfunction "2_2") (pintype "bidirectional"))
      (node (ref "U4") (pin "18") (pinfunction "B2_18") (pintype "bidirectional"))
    )
    (net (code "46") (name "/IO18") (class "Default")
      (node (ref "J12") (pin "3") (pinfunction "3_3") (pintype "bidirectional"))
      (node (ref "J8") (pin "3") (pinfunction "P$3_3") (pintype "bidirectional"))
      (node (ref "U4") (pin "17") (pinfunction "B3_17") (pintype "bidirectional"))
    )
    (net (code "47") (name "/IO21") (class "Default")
      (node (ref "J12") (pin "4") (pinfunction "4_4") (pintype "bidirectional"))
      (node (ref "U4") (pin "16") (pinfunction "B4_16") (pintype "bidirectional"))
    )
    (net (code "48") (name "/IO22") (class "Default")
      (node (ref "24L01-PI") (pin "2") (pinfunction "2_2") (pintype "bidirectional"))
      (node (ref "J12") (pin "5") (pinfunction "5_5") (pintype "bidirectional"))
      (node (ref "U4") (pin "15") (pinfunction "B5_15") (pintype "bidirectional"))
    )
    (net (code "49") (name "/IO23") (class "Default")
      (node (ref "J12") (pin "6") (pinfunction "6_6") (pintype "bidirectional"))
      (node (ref "PINTPI") (pin "1") (pinfunction "1_1") (pintype "bidirectional"))
      (node (ref "U4") (pin "14") (pinfunction "B6_14") (pintype "bidirectional"))
    )
    (net (code "50") (name "/IO24") (class "Default")
      (node (ref "J12") (pin "7") (pinfunction "7_7") (pintype "bidirectional"))
      (node (ref "SPI-OLED-PI") (pin "6") (pinfunction "6_6") (pintype "bidirectional"))
      (node (ref "U4") (pin "13") (pinfunction "B7_13") (pintype "bidirectional"))
    )
    (net (code "51") (name "/IO25") (class "Default")
      (node (ref "J12") (pin "8") (pinfunction "8_8") (pintype "bidirectional"))
      (node (ref "PI2C") (pin "00") (pinfunction "L_00") (pintype "bidirectional"))
      (node (ref "SPI-OLED-PI") (pin "7") (pinfunction "7_7") (pintype "bidirectional"))
      (node (ref "U4") (pin "12") (pinfunction "B8_12") (pintype "bidirectional"))
    )
    (net (code "52") (name "/IO28") (class "Default")
      (node (ref "J11") (pin "1") (pinfunction "P$1_1") (pintype "bidirectional"))
      (node (ref "PLED3") (pin "00") (pinfunction "L_00") (pintype "bidirectional"))
      (node (ref "U3") (pin "13") (pinfunction "B1_13") (pintype "bidirectional"))
    )
    (net (code "53") (name "/IO29") (class "Default")
      (node (ref "J11") (pin "2") (pinfunction "P$2_2") (pintype "bidirectional"))
      (node (ref "U3") (pin "12") (pinfunction "B2_12") (pintype "bidirectional"))
    )
    (net (code "54") (name "/IO30") (class "Default")
      (node (ref "J11") (pin "3") (pinfunction "P$3_3") (pintype "bidirectional"))
      (node (ref "U3") (pin "11") (pinfunction "B3_11") (pintype "bidirectional"))
    )
    (net (code "55") (name "/IO31") (class "Default")
      (node (ref "J11") (pin "4") (pinfunction "P$4_4") (pintype "bidirectional"))
      (node (ref "U3") (pin "10") (pinfunction "B4_10") (pintype "bidirectional"))
    )
    (net (code "56") (name "/IRQ") (class "Default")
      (node (ref "24L01") (pin "5") (pinfunction "5_5") (pintype "bidirectional"))
      (node (ref "24L01-PI") (pin "5") (pinfunction "5_5") (pintype "bidirectional"))
      (node (ref "PINT") (pin "2") (pinfunction "2_2") (pintype "bidirectional"))
      (node (ref "PINTPI") (pin "2") (pinfunction "2_2") (pintype "bidirectional"))
    )
    (net (code "57") (name "/MISO") (class "Default")
      (node (ref "24L01-PI") (pin "4") (pinfunction "4_4") (pintype "bidirectional"))
      (node (ref "J13") (pin "4") (pinfunction "4_4") (pintype "bidirectional"))
      (node (ref "PMISO") (pin "1") (pinfunction "1_1") (pintype "bidirectional"))
      (node (ref "U5") (pin "16") (pinfunction "B4_16") (pintype "bidirectional"))
    )
    (net (code "58") (name "/MISO-PI") (class "Default")
      (node (ref "PI-P1") (pin "21") (pinfunction "SPI_MISO_21") (pintype "input"))
      (node (ref "U5") (pin "5") (pinfunction "A4_5") (pintype "bidirectional"))
    )
    (net (code "59") (name "/MOSI") (class "Default")
      (node (ref "24L01-PI") (pin "6") (pinfunction "6_6") (pintype "bidirectional"))
      (node (ref "J13") (pin "3") (pinfunction "3_3") (pintype "bidirectional"))
      (node (ref "PMOSI") (pin "1") (pinfunction "1_1") (pintype "bidirectional"))
      (node (ref "SPI-OLED-PI") (pin "4") (pinfunction "4_4") (pintype "bidirectional"))
      (node (ref "U5") (pin "17") (pinfunction "B3_17") (pintype "bidirectional"))
    )
    (net (code "60") (name "/MOSI-PI") (class "Default")
      (node (ref "PI-P1") (pin "19") (pinfunction "SPI_MOSI_19") (pintype "output"))
      (node (ref "U5") (pin "4") (pinfunction "A3_4") (pintype "bidirectional"))
    )
    (net (code "61") (name "/OLED-RST") (class "Default")
      (node (ref "I2C-OLED") (pin "4") (pinfunction "4_4") (pintype "bidirectional"))
      (node (ref "PI2C") (pin "MM") (pinfunction "C_MM") (pintype "bidirectional"))
    )
    (net (code "62") (name "/OW") (class "Default")
      (node (ref "IC2") (pin "2") (pinfunction "1W_2") (pintype "open_collector"))
      (node (ref "JP2") (pin "2") (pinfunction "P$2_2") (pintype "bidirectional"))
      (node (ref "JP3") (pin "2") (pinfunction "P$2_2") (pintype "bidirectional"))
      (node (ref "JP4") (pin "2") (pinfunction "P$2_2") (pintype "bidirectional"))
      (node (ref "Q5") (pin "3") (pinfunction "D_3") (pintype "passive"))
    )
    (net (code "63") (name "/RESET") (class "Default")
      (node (ref "C1") (pin "1") (pinfunction "1_1") (pintype "passive"))
      (node (ref "IC1") (pin "1") (pinfunction "PC6(/RESET)_1") (pintype "bidirectional"))
      (node (ref "POWER") (pin "6") (pinfunction "6_6") (pintype "bidirectional"))
      (node (ref "R2") (pin "2") (pinfunction "2_2") (pintype "passive"))
      (node (ref "RESET") (pin "2") (pinfunction "2_2") (pintype "bidirectional"))
      (node (ref "U6") (pin "28") (pinfunction "RESET_28") (pintype "bidirectional"))
      (node (ref "U6") (pin "34") (pinfunction "RST_34") (pintype "bidirectional"))
    )
    (net (code "64") (name "/RXD") (class "Default")
      (node (ref "JRXD") (pin "1") (pinfunction "1_1") (pintype "bidirectional"))
      (node (ref "PI-SERIAL") (pin "1") (pinfunction "1_1") (pintype "bidirectional"))
      (node (ref "Q7") (pin "2") (pinfunction "S_2") (pintype "passive"))
      (node (ref "STINFO") (pin "11") (pinfunction "R_11") (pintype "bidirectional"))
    )
    (net (code "65") (name "/RXD-PI") (class "Default")
      (node (ref "PI-P1") (pin "10") (pinfunction "RXD_10") (pintype "input"))
      (node (ref "Q6") (pin "2") (pinfunction "S_2") (pintype "passive"))
    )
    (net (code "66") (name "/SCL") (class "Default")
      (node (ref "I2C") (pin "1") (pinfunction "1_1") (pintype "bidirectional"))
      (node (ref "I2C-OLED") (pin "5") (pinfunction "5_5") (pintype "bidirectional"))
      (node (ref "IC2") (pin "4") (pinfunction "SCL_4") (pintype "input"))
      (node (ref "PSCL") (pin "2") (pinfunction "2_2") (pintype "bidirectional"))
      (node (ref "Q2") (pin "2") (pinfunction "S_2") (pintype "passive"))
      (node (ref "R5") (pin "1") (pinfunction "1_1") (pintype "passive"))
    )
    (net (code "67") (name "/SCL-PI") (class "Default")
      (node (ref "PI-P1") (pin "5") (pinfunction "SCL0_5") (pintype "output"))
      (node (ref "Q4") (pin "2") (pinfunction "S_2") (pintype "passive"))
    )
    (net (code "68") (name "/SCLK") (class "Default")
      (node (ref "24L01-PI") (pin "3") (pinfunction "3_3") (pintype "bidirectional"))
      (node (ref "J13") (pin "5") (pinfunction "5_5") (pintype "bidirectional"))
      (node (ref "PCLK") (pin "1") (pinfunction "1_1") (pintype "bidirectional"))
      (node (ref "SPI-OLED-PI") (pin "5") (pinfunction "5_5") (pintype "bidirectional"))
      (node (ref "U5") (pin "15") (pinfunction "B5_15") (pintype "bidirectional"))
    )
    (net (code "69") (name "/SCLK-PI") (class "Default")
      (node (ref "PI-P1") (pin "23") (pinfunction "SPI_SCLK_23") (pintype "output"))
      (node (ref "U5") (pin "6") (pinfunction "A5_6") (pintype "bidirectional"))
    )
    (net (code "70") (name "/SDA") (class "Default")
      (node (ref "I2C") (pin "2") (pinfunction "2_2") (pintype "bidirectional"))
      (node (ref "I2C-OLED") (pin "6") (pinfunction "6_6") (pintype "bidirectional"))
      (node (ref "IC2") (pin "5") (pinfunction "SDA_5") (pintype "bidirectional"))
      (node (ref "PSDA") (pin "2") (pinfunction "2_2") (pintype "bidirectional"))
      (node (ref "Q1") (pin "2") (pinfunction "S_2") (pintype "passive"))
      (node (ref "R4") (pin "1") (pinfunction "1_1") (pintype "passive"))
    )
    (net (code "71") (name "/SDA-PI") (class "Default")
      (node (ref "PI-P1") (pin "3") (pinfunction "SDA0_3") (pintype "bidirectional"))
      (node (ref "Q3") (pin "2") (pinfunction "S_2") (pintype "passive"))
    )
    (net (code "72") (name "/SPI_CE0") (class "Default")
      (node (ref "PI-P1") (pin "24") (pinfunction "#SPI_CE0_24") (pintype "output"))
      (node (ref "U5") (pin "7") (pinfunction "A6_7") (pintype "bidirectional"))
    )
    (net (code "73") (name "/SPI_CE1") (class "Default")
      (node (ref "PI-P1") (pin "26") (pinfunction "#SPI_CE1_26") (pintype "output"))
      (node (ref "U5") (pin "8") (pinfunction "A7_8") (pintype "bidirectional"))
    )
    (net (code "74") (name "/TXD") (class "Default")
      (node (ref "J13") (pin "1") (pinfunction "1_1") (pintype "bidirectional"))
      (node (ref "JTXD") (pin "1") (pinfunction "1_1") (pintype "bidirectional"))
      (node (ref "PI-SERIAL") (pin "2") (pinfunction "2_2") (pintype "bidirectional"))
      (node (ref "U5") (pin "20") (pinfunction "B1_20") (pintype "bidirectional"))
    )
    (net (code "75") (name "/TXD-PI") (class "Default")
      (node (ref "PI-P1") (pin "8") (pinfunction "TXD_8") (pintype "output"))
      (node (ref "U5") (pin "1") (pinfunction "A1_1") (pintype "bidirectional"))
    )
    (net (code "76") (name "/VIN") (class "Default")
      (node (ref "C6") (pin "+") (pinfunction "+_+") (pintype "passive"))
      (node (ref "D1") (pin "-") (pinfunction "-_-") (pintype "passive"))
      (node (ref "POWER") (pin "1") (pinfunction "1_1") (pintype "bidirectional"))
      (node (ref "PPWM") (pin "11") (pinfunction "R_11") (pintype "bidirectional"))
      (node (ref "U1") (pin "1") (pinfunction "IN_1") (pintype "bidirectional"))
      (node (ref "U6") (pin "23") (pinfunction "VIN_23") (pintype "bidirectional"))
    )
    (net (code "77") (name "3V3-EXT") (class "Default")
      (node (ref "C10") (pin "2") (pinfunction "2_2") (pintype "passive"))
      (node (ref "PI_VCC_EXT") (pin "CH1B") (pinfunction "CH1B_CH1B") (pintype "bidirectional"))
      (node (ref "U2") (pin "2") (pinfunction "OUT_2") (pintype "bidirectional"))
      (node (ref "U2") (pin "TER") (pinfunction "TAB_TER") (pintype "bidirectional"))
    )
    (net (code "78") (name "3V3-PI") (class "Default")
      (node (ref "C11") (pin "1") (pinfunction "1_1") (pintype "passive"))
      (node (ref "C12") (pin "1") (pinfunction "1_1") (pintype "passive"))
      (node (ref "C13") (pin "1") (pinfunction "1_1") (pintype "passive"))
      (node (ref "PI-P1") (pin "1") (pinfunction "3.3V_1") (pintype "power_in"))
      (node (ref "PI-P1") (pin "P5.2") (pinfunction "3.3V_P5.2") (pintype "power_in"))
      (node (ref "PI_VCC_EXT") (pin "CH1A") (pinfunction "CH1A_CH1A") (pintype "bidirectional"))
      (node (ref "Q3") (pin "1") (pinfunction "G_1") (pintype "passive"))
      (node (ref "Q4") (pin "1") (pinfunction "G_1") (pintype "passive"))
      (node (ref "Q6") (pin "1") (pinfunction "G_1") (pintype "passive"))
      (node (ref "U3") (pin "1") (pinfunction "VCCA_1") (pintype "bidirectional"))
      (node (ref "U3") (pin "8") (pinfunction "OE_8") (pintype "bidirectional"))
      (node (ref "U4") (pin "10") (pinfunction "OE_10") (pintype "bidirectional"))
      (node (ref "U4") (pin "2") (pinfunction "VCCA_2") (pintype "bidirectional"))
      (node (ref "U5") (pin "10") (pinfunction "OE_10") (pintype "bidirectional"))
      (node (ref "U5") (pin "2") (pinfunction "VCCA_2") (pintype "bidirectional"))
    )
    (net (code "79") (name "5V-EXT") (class "Default")
      (node (ref "C7") (pin "+") (pinfunction "+_+") (pintype "passive"))
      (node (ref "C8") (pin "2") (pinfunction "2_2") (pintype "passive"))
      (node (ref "JVDD") (pin "1") (pinfunction "1_1") (pintype "bidirectional"))
      (node (ref "PI_VCC_EXT") (pin "CH2B") (pinfunction "CH2B_CH2B") (pintype "bidirectional"))
      (node (ref "U1") (pin "2") (pinfunction "OUT_2") (pintype "bidirectional"))
      (node (ref "U2") (pin "3") (pinfunction "IN_3") (pintype "bidirectional"))
    )
    (net (code "80") (name "5V-PI") (class "Default")
      (node (ref "PI-P1") (pin "2") (pinfunction "5.0V_2") (pintype "power_in"))
      (node (ref "PI-P1") (pin "P5.1") (pinfunction "5.0V_P5.1") (pintype "power_in"))
      (node (ref "PI_VCC_EXT") (pin "CH2A") (pinfunction "CH2A_CH2A") (pintype "bidirectional"))
      (node (ref "PLED2") (pin "11") (pinfunction "R_11") (pintype "bidirectional"))
    )
    (net (code "81") (name "GND") (class "Default")
      (node (ref "24L01") (pin "1") (pinfunction "1_1") (pintype "bidirectional"))
      (node (ref "24L01-PI") (pin "1") (pinfunction "1_1") (pintype "bidirectional"))
      (node (ref "ARDUINO-SERIAL") (pin "4") (pinfunction "4_4") (pintype "bidirectional"))
      (node (ref "C10") (pin "1") (pinfunction "1_1") (pintype "passive"))
      (node (ref "C11") (pin "2") (pinfunction "2_2") (pintype "passive"))
      (node (ref "C12") (pin "2") (pinfunction "2_2") (pintype "passive"))
      (node (ref "C13") (pin "2") (pinfunction "2_2") (pintype "passive"))
      (node (ref "C14") (pin "2") (pinfunction "2_2") (pintype "passive"))
      (node (ref "C15") (pin "2") (pinfunction "2_2") (pintype "passive"))
      (node (ref "C16") (pin "2") (pinfunction "2_2") (pintype "passive"))
      (node (ref "C2") (pin "2") (pinfunction "2_2") (pintype "passive"))
      (node (ref "C3") (pin "2") (pinfunction "2_2") (pintype "passive"))
      (node (ref "C4") (pin "1") (pinfunction "1_1") (pintype "passive"))
      (node (ref "C5") (pin "2") (pinfunction "2_2") (pintype "passive"))
      (node (ref "C6") (pin "-") (pinfunction "-_-") (pintype "passive"))
      (node (ref "C7") (pin "-") (pinfunction "-_-") (pintype "passive"))
      (node (ref "C8") (pin "1") (pinfunction "1_1") (pintype "passive"))
      (node (ref "C9") (pin "2") (pinfunction "2_2") (pintype "passive"))
      (node (ref "I2C") (pin "4") (pinfunction "4_4") (pintype "bidirectional"))
      (node (ref "I2C-OLED") (pin "3") (pinfunction "3_3") (pintype "bidirectional"))
      (node (ref "IC1") (pin "22") (pinfunction "AGND_22") (pintype "bidirectional"))
      (node (ref "IC1") (pin "8") (pinfunction "GND_8") (pintype "bidirectional"))
      (node (ref "IC2") (pin "3") (pinfunction "GND_3") (pintype "power_in"))
      (node (ref "J1") (pin "5") (pinfunction "5_5") (pintype "bidirectional"))
      (node (ref "J1") (pin "6") (pinfunction "6_6") (pintype "bidirectional"))
      (node (ref "J2") (pin "2") (pinfunction "P$2_2") (pintype "bidirectional"))
      (node (ref "J3") (pin "2") (pinfunction "P$2_2") (pintype "bidirectional"))
      (node (ref "J4") (pin "2") (pinfunction "P$2_2") (pintype "bidirectional"))
      (node (ref "J5") (pin "2") (pinfunction "P$2_2") (pintype "bidirectional"))
      (node (ref "J6") (pin "2") (pinfunction "P$2_2") (pintype "bidirectional"))
      (node (ref "J7") (pin "2") (pinfunction "P$2_2") (pintype "bidirectional"))
      (node (ref "J8") (pin "2") (pinfunction "P$2_2") (pintype "bidirectional"))
      (node (ref "J9") (pin "-") (pinfunction "-_-") (pintype "bidirectional"))
      (node (ref "J9") (pin "CDN") (pinfunction "CDN_CDN") (pintype "bidirectional"))
      (node (ref "JP2") (pin "3") (pinfunction "P$3_3") (pintype "bidirectional"))
      (node (ref "JP3") (pin "3") (pinfunction "P$3_3") (pintype "bidirectional"))
      (node (ref "JP4") (pin "3") (pinfunction "P$3_3") (pintype "bidirectional"))
      (node (ref "LED1") (pin "-") (pinfunction "-_-") (pintype "passive"))
      (node (ref "LED2") (pin "-") (pinfunction "-_-") (pintype "passive"))
      (node (ref "LED3") (pin "-") (pinfunction "-_-") (pintype "passive"))
      (node (ref "OK1") (pin "3") (pinfunction "E_3") (pintype "passive"))
      (node (ref "PB1") (pin "7") (pinfunction "7_7") (pintype "bidirectional"))
      (node (ref "PI-P1") (pin "6") (pinfunction "GND_6") (pintype "power_in"))
      (node (ref "PI-P1") (pin "P5.7") (pinfunction "GND_P5.7") (pintype "power_in"))
      (node (ref "PI-P1") (pin "P5.8") (pinfunction "GND_P5.8") (pintype "power_in"))
      (node (ref "PI-SERIAL") (pin "4") (pinfunction "4_4") (pintype "bidirectional"))
      (node (ref "POWER") (pin "2") (pinfunction "2_2") (pintype "bidirectional"))
      (node (ref "POWER") (pin "3") (pinfunction "3_3") (pintype "bidirectional"))
      (node (ref "R6") (pin "1") (pinfunction "1_1") (pintype "passive"))
      (node (ref "R7") (pin "1") (pinfunction "1_1") (pintype "passive"))
      (node (ref "RESET") (pin "1") (pinfunction "1_1") (pintype "bidirectional"))
      (node (ref "RESET") (pin "S1") (pinfunction "S1_S1") (pintype "bidirectional"))
      (node (ref "RESET") (pin "S2") (pinfunction "S2_S2") (pintype "bidirectional"))
      (node (ref "SPI-OLED") (pin "1") (pinfunction "1_1") (pintype "bidirectional"))
      (node (ref "SPI-OLED-PI") (pin "1") (pinfunction "1_1") (pintype "bidirectional"))
      (node (ref "U1") (pin "3") (pinfunction "GND_3") (pintype "bidirectional"))
      (node (ref "U2") (pin "1") (pinfunction "GND_1") (pintype "bidirectional"))
      (node (ref "U3") (pin "7") (pinfunction "GND_7") (pintype "bidirectional"))
      (node (ref "U4") (pin "11") (pinfunction "GND_11") (pintype "bidirectional"))
      (node (ref "U5") (pin "11") (pinfunction "GND_11") (pintype "bidirectional"))
      (node (ref "U6") (pin "15") (pinfunction "GND_15") (pintype "bidirectional"))
      (node (ref "U6") (pin "24") (pinfunction "GND_24") (pintype "bidirectional"))
      (node (ref "U6") (pin "25") (pinfunction "GND_25") (pintype "bidirectional"))
      (node (ref "U6") (pin "33") (pinfunction "GND_33") (pintype "bidirectional"))
    )
    (net (code "82") (name "Net-(D1-Pad+)") (class "Default")
      (node (ref "D1") (pin "+") (pinfunction "+_+") (pintype "passive"))
      (node (ref "J9") (pin "+") (pinfunction "+_+") (pintype "bidirectional"))
    )
    (net (code "83") (name "Net-(IC1-PB6(XTAL1{slash}TOSC1))") (class "Default")
      (node (ref "C2") (pin "1") (pinfunction "1_1") (pintype "passive"))
      (node (ref "IC1") (pin "9") (pinfunction "PB6(XTAL1/TOSC1)_9") (pintype "bidirectional"))
      (node (ref "X1") (pin "2") (pinfunction "2_2") (pintype "passive"))
    )
    (net (code "84") (name "Net-(IC1-PB7(XTAL2{slash}TOSC2))") (class "Default")
      (node (ref "C3") (pin "1") (pinfunction "1_1") (pintype "passive"))
      (node (ref "IC1") (pin "10") (pinfunction "PB7(XTAL2/TOSC2)_10") (pintype "bidirectional"))
      (node (ref "X1") (pin "1") (pinfunction "1_1") (pintype "passive"))
    )
    (net (code "85") (name "Net-(IC2A-AD0)") (class "Default")
      (node (ref "IC2") (pin "8") (pinfunction "AD0_8") (pintype "input"))
      (node (ref "PAD2") (pin "1") (pinfunction "1_1") (pintype "bidirectional"))
      (node (ref "R6") (pin "2") (pinfunction "2_2") (pintype "passive"))
    )
    (net (code "86") (name "Net-(IC2A-AD1)") (class "Default")
      (node (ref "IC2") (pin "7") (pinfunction "AD1_7") (pintype "input"))
      (node (ref "PAD1") (pin "1") (pinfunction "1_1") (pintype "bidirectional"))
      (node (ref "R7") (pin "2") (pinfunction "2_2") (pintype "passive"))
    )
    (net (code "87") (name "Net-(IC2A-PCT)") (class "Default")
      (node (ref "IC2") (pin "6") (pinfunction "PCT_6") (pintype "output"))
      (node (ref "Q5") (pin "1") (pinfunction "G_1") (pintype "passive"))
    )
    (net (code "88") (name "Net-(J1-Pad4)") (class "Default")
      (node (ref "J1") (pin "4") (pinfunction "4_4") (pintype "bidirectional"))
      (node (ref "JVDD") (pin "2") (pinfunction "2_2") (pintype "bidirectional"))
    )
    (net (code "89") (name "Net-(J2-P$1)") (class "Default")
      (node (ref "J2") (pin "1") (pinfunction "P$1_1") (pintype "bidirectional"))
      (node (ref "J3") (pin "1") (pinfunction "P$1_1") (pintype "bidirectional"))
      (node (ref "J4") (pin "1") (pinfunction "P$1_1") (pintype "bidirectional"))
      (node (ref "J5") (pin "1") (pinfunction "P$1_1") (pintype "bidirectional"))
      (node (ref "J6") (pin "1") (pinfunction "P$1_1") (pintype "bidirectional"))
      (node (ref "J7") (pin "1") (pinfunction "P$1_1") (pintype "bidirectional"))
      (node (ref "J8") (pin "1") (pinfunction "P$1_1") (pintype "bidirectional"))
      (node (ref "PPWM") (pin "MM") (pinfunction "C_MM") (pintype "bidirectional"))
    )
    (net (code "90") (name "Net-(J14-Pad2)") (class "Default")
      (node (ref "J14") (pin "2") (pinfunction "2_2") (pintype "bidirectional"))
      (node (ref "R1") (pin "2") (pinfunction "2_2") (pintype "passive"))
    )
    (net (code "91") (name "Net-(LED1-Pad+)") (class "Default")
      (node (ref "LED1") (pin "+") (pinfunction "+_+") (pintype "passive"))
      (node (ref "R9") (pin "2") (pinfunction "2_2") (pintype "passive"))
    )
    (net (code "92") (name "Net-(LED2-Pad+)") (class "Default")
      (node (ref "LED2") (pin "+") (pinfunction "+_+") (pintype "passive"))
      (node (ref "R10") (pin "2") (pinfunction "2_2") (pintype "passive"))
    )
    (net (code "93") (name "Net-(LED3-Pad+)") (class "Default")
      (node (ref "LED3") (pin "+") (pinfunction "+_+") (pintype "passive"))
      (node (ref "R11") (pin "2") (pinfunction "2_2") (pintype "passive"))
    )
    (net (code "94") (name "Net-(OK1-AC1)") (class "Default")
      (node (ref "OK1") (pin "1") (pinfunction "AC1_1") (pintype "passive"))
      (node (ref "R1") (pin "1") (pinfunction "1_1") (pintype "passive"))
    )
    (net (code "95") (name "Net-(OK1-AC2)") (class "Default")
      (node (ref "J14") (pin "1") (pinfunction "1_1") (pintype "bidirectional"))
      (node (ref "OK1") (pin "2") (pinfunction "AC2_2") (pintype "passive"))
    )
    (net (code "96") (name "Net-(OK1-C)") (class "Default")
      (node (ref "OK1") (pin "4") (pinfunction "C_4") (pintype "passive"))
      (node (ref "STINFO") (pin "MM") (pinfunction "C_MM") (pintype "bidirectional"))
    )
    (net (code "97") (name "Net-(PLED1-C)") (class "Default")
      (node (ref "PLED1") (pin "MM") (pinfunction "C_MM") (pintype "bidirectional"))
      (node (ref "R9") (pin "1") (pinfunction "1_1") (pintype "passive"))
    )
    (net (code "98") (name "Net-(PLED2-C)") (class "Default")
      (node (ref "PLED2") (pin "MM") (pinfunction "C_MM") (pintype "bidirectional"))
      (node (ref "R10") (pin "1") (pinfunction "1_1") (pintype "passive"))
    )
    (net (code "99") (name "Net-(PLED3-C)") (class "Default")
      (node (ref "PLED3") (pin "MM") (pinfunction "C_MM") (pintype "bidirectional"))
      (node (ref "R11") (pin "1") (pinfunction "1_1") (pintype "passive"))
    )
    (net (code "100") (name "Net-(PSSPI-C)") (class "Default")
      (node (ref "PSSPI") (pin "MM") (pinfunction "C_MM") (pintype "bidirectional"))
      (node (ref "SPI-OLED-PI") (pin "8") (pinfunction "8_8") (pintype "bidirectional"))
    )
    (net (code "101") (name "Net-(Q1-D)") (class "Default")
      (node (ref "Q1") (pin "3") (pinfunction "D_3") (pintype "passive"))
      (node (ref "Q3") (pin "3") (pinfunction "D_3") (pintype "passive"))
    )
    (net (code "102") (name "Net-(Q2-D)") (class "Default")
      (node (ref "Q2") (pin "3") (pinfunction "D_3") (pintype "passive"))
      (node (ref "Q4") (pin "3") (pinfunction "D_3") (pintype "passive"))
    )
    (net (code "103") (name "Net-(Q6-D)") (class "Default")
      (node (ref "Q6") (pin "3") (pinfunction "D_3") (pintype "passive"))
      (node (ref "Q7") (pin "3") (pinfunction "D_3") (pintype "passive"))
    )
    (net (code "104") (name "VDD") (class "Default")
      (node (ref "3V3_VDD_5V") (pin "COM1") (pinfunction "COM1_COM1") (pintype "bidirectional"))
      (node (ref "3V3_VDD_5V") (pin "COM2") (pinfunction "COM2_COM2") (pintype "bidirectional"))
      (node (ref "ARDUINO-SERIAL") (pin "3") (pinfunction "3_3") (pintype "bidirectional"))
      (node (ref "C14") (pin "1") (pinfunction "1_1") (pintype "passive"))
      (node (ref "C15") (pin "1") (pinfunction "1_1") (pintype "passive"))
      (node (ref "C16") (pin "1") (pinfunction "1_1") (pintype "passive"))
      (node (ref "C4") (pin "2") (pinfunction "2_2") (pintype "passive"))
      (node (ref "C9") (pin "1") (pinfunction "1_1") (pintype "passive"))
      (node (ref "I2C") (pin "3") (pinfunction "3_3") (pintype "bidirectional"))
      (node (ref "I2C-OLED") (pin "1") (pinfunction "1_1") (pintype "bidirectional"))
      (node (ref "IC1") (pin "20") (pinfunction "AVCC_20") (pintype "bidirectional"))
      (node (ref "IC1") (pin "7") (pinfunction "VCC_7") (pintype "bidirectional"))
      (node (ref "IC2") (pin "1") (pinfunction "VDD_1") (pintype "power_in"))
      (node (ref "JP2") (pin "1") (pinfunction "P$1_1") (pintype "bidirectional"))
      (node (ref "JP3") (pin "1") (pinfunction "P$1_1") (pintype "bidirectional"))
      (node (ref "JP4") (pin "1") (pinfunction "P$1_1") (pintype "bidirectional"))
      (node (ref "PAD1") (pin "2") (pinfunction "2_2") (pintype "bidirectional"))
      (node (ref "PAD2") (pin "2") (pinfunction "2_2") (pintype "bidirectional"))
      (node (ref "PI-SERIAL") (pin "3") (pinfunction "3_3") (pintype "bidirectional"))
      (node (ref "PLED2") (pin "00") (pinfunction "L_00") (pintype "bidirectional"))
      (node (ref "POWER") (pin "4") (pinfunction "4_4") (pintype "bidirectional"))
      (node (ref "PPWM") (pin "00") (pinfunction "L_00") (pintype "bidirectional"))
      (node (ref "Q1") (pin "1") (pinfunction "G_1") (pintype "passive"))
      (node (ref "Q2") (pin "1") (pinfunction "G_1") (pintype "passive"))
      (node (ref "Q5") (pin "2") (pinfunction "S_2") (pintype "passive"))
      (node (ref "Q7") (pin "1") (pinfunction "G_1") (pintype "passive"))
      (node (ref "R2") (pin "1") (pinfunction "1_1") (pintype "passive"))
      (node (ref "R4") (pin "2") (pinfunction "2_2") (pintype "passive"))
      (node (ref "R5") (pin "2") (pinfunction "2_2") (pintype "passive"))
      (node (ref "SPI-OLED") (pin "3") (pinfunction "3_3") (pintype "bidirectional"))
      (node (ref "SPI-OLED-PI") (pin "3") (pinfunction "3_3") (pintype "bidirectional"))
      (node (ref "U3") (pin "14") (pinfunction "VCCB_14") (pintype "bidirectional"))
      (node (ref "U4") (pin "19") (pinfunction "VCCB_19") (pintype "bidirectional"))
      (node (ref "U5") (pin "19") (pinfunction "VCCB_19") (pintype "bidirectional"))
      (node (ref "U6") (pin "26") (pinfunction "5V_26") (pintype "bidirectional"))
      (node (ref "U6") (pin "31") (pinfunction "VCC_31") (pintype "bidirectional"))
    )
    (net (code "105") (name "unconnected-(I2C-OLED-Pad2)") (class "Default")
      (node (ref "I2C-OLED") (pin "2") (pinfunction "2_2") (pintype "bidirectional"))
    )
    (net (code "106") (name "unconnected-(IC1-AREF-Pad21)") (class "Default")
      (node (ref "IC1") (pin "21") (pinfunction "AREF_21") (pintype "bidirectional"))
    )
    (net (code "107") (name "unconnected-(PI-P1-DNC-Pad4)") (class "Default")
      (node (ref "PI-P1") (pin "4") (pinfunction "DNC_4") (pintype "no_connect"))
    )
    (net (code "108") (name "unconnected-(PI-P1-DNC-Pad9)") (class "Default")
      (node (ref "PI-P1") (pin "9") (pinfunction "DNC_9") (pintype "no_connect"))
    )
    (net (code "109") (name "unconnected-(PI-P1-DNC-Pad14)") (class "Default")
      (node (ref "PI-P1") (pin "14") (pinfunction "DNC_14") (pintype "no_connect"))
    )
    (net (code "110") (name "unconnected-(PI-P1-DNC-Pad17)") (class "Default")
      (node (ref "PI-P1") (pin "17") (pinfunction "DNC_17") (pintype "no_connect"))
    )
    (net (code "111") (name "unconnected-(PI-P1-DNC-Pad20)") (class "Default")
      (node (ref "PI-P1") (pin "20") (pinfunction "DNC_20") (pintype "no_connect"))
    )
    (net (code "112") (name "unconnected-(PI-P1-DNC-Pad25)") (class "Default")
      (node (ref "PI-P1") (pin "25") (pinfunction "DNC_25") (pintype "no_connect"))
    )
    (net (code "113") (name "unconnected-(SPI-OLED-PI-Pad2)") (class "Default")
      (node (ref "SPI-OLED-PI") (pin "2") (pinfunction "2_2") (pintype "bidirectional"))
    )
    (net (code "114") (name "unconnected-(SPI-OLED-Pad2)") (class "Default")
      (node (ref "SPI-OLED") (pin "2") (pinfunction "2_2") (pintype "bidirectional"))
    )
  )
)
